# FPGAConfig.net
KiCad netlist of a schematic drawn in Altium Designer
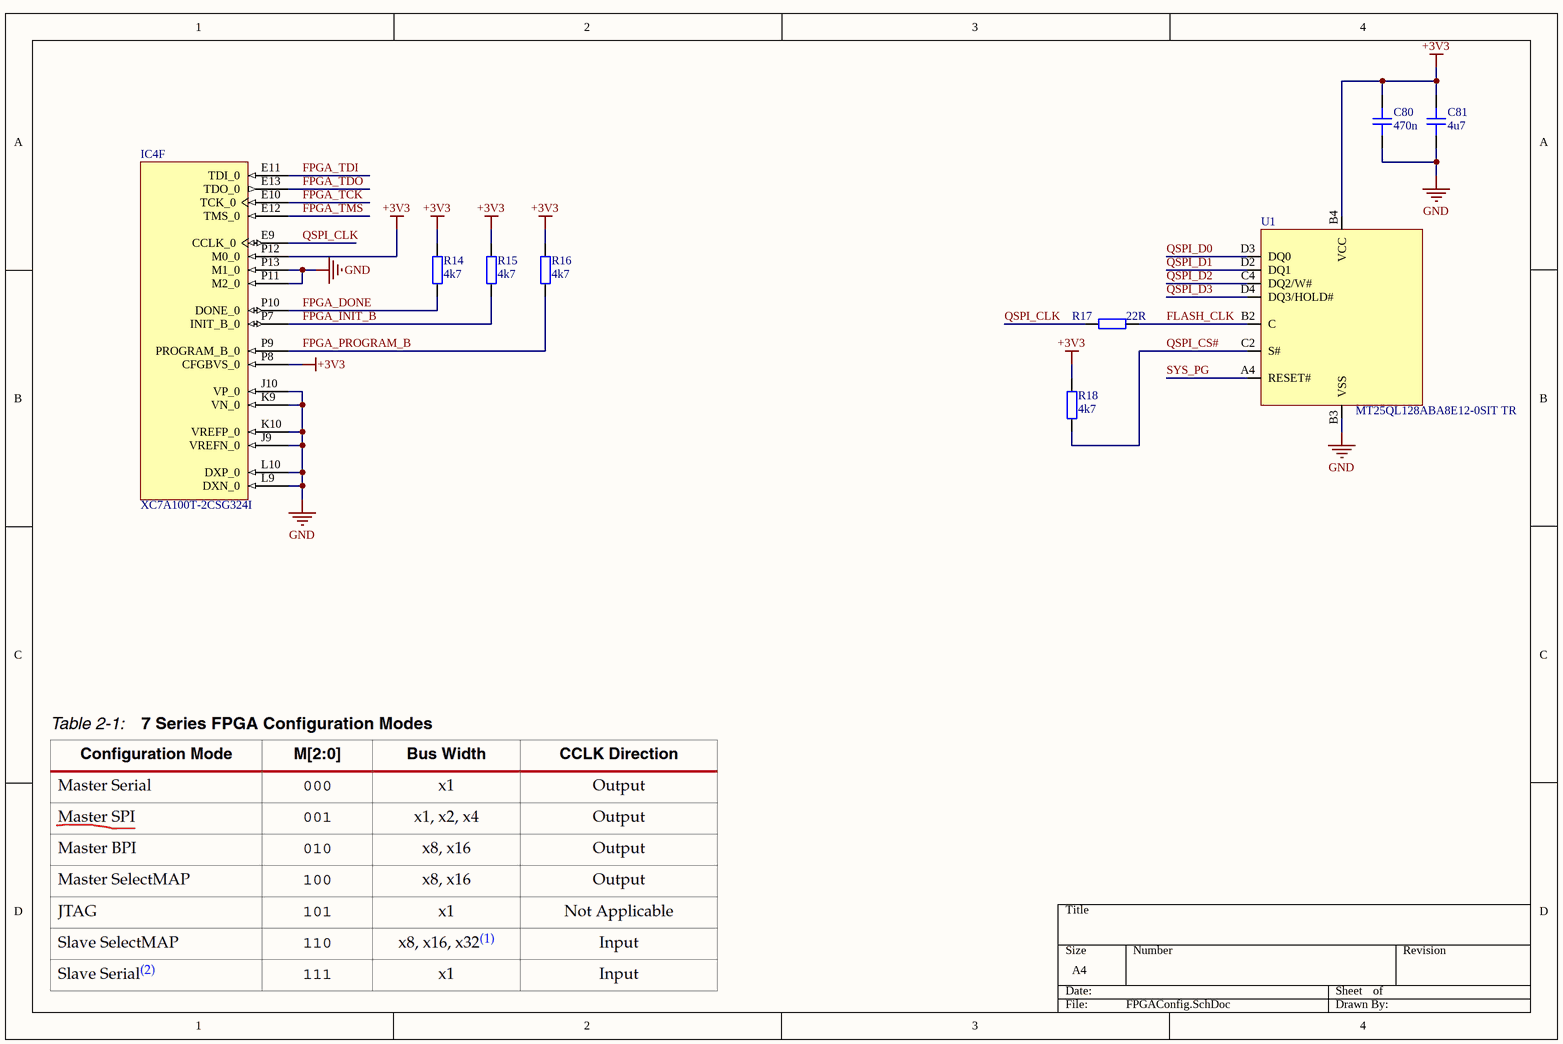
[diagram p0: FPGAConfig.SchDoc]

(export (version "E")
  (design (tool "Eeschema 10.0.6"))
  (components
    (comp (ref "C80")
      (value "470n")
      (footprint "CAP_0201")
      (description "Capacitor SMD 0201")
      (libsource (lib "Schematic-Lib-PhilsLab") (part "CAP_0201"))
    )
    (comp (ref "C81")
      (value "4u7")
      (footprint "CAP_0402")
      (description "Capacitor SMD 0402")
      (libsource (lib "Schematic-Lib-PhilsLab") (part "CAP_0402"))
    )
    (comp (ref "IC4")
      (value "XC7A100T-2CSG324I")
      (footprint "CSG324")
      (description "Artix-7 FPGA, 210 User I/Os, 0 GTP, 324-Ball BGA, Speed Grade 2, Industrial Grade, Pb-Free")
      (fields (field (name "GENERIC PART NUMBER") "XC7A100T") (field (name "MANUFACTURER") "Xilinx"))
      (libsource (lib "Schematic-Lib-PhilsLab") (part "XC7A100T-2CSG324I"))
    )
    (comp (ref "R14")
      (value "4k7")
      (footprint "RES_0201")
      (description "Resistor SMD 0201")
      (libsource (lib "Schematic-Lib-PhilsLab") (part "RES_0201"))
    )
    (comp (ref "R15")
      (value "4k7")
      (footprint "RES_0201")
      (description "Resistor SMD 0201")
      (libsource (lib "Schematic-Lib-PhilsLab") (part "RES_0201"))
    )
    (comp (ref "R16")
      (value "4k7")
      (footprint "RES_0201")
      (description "Resistor SMD 0201")
      (libsource (lib "Schematic-Lib-PhilsLab") (part "RES_0201"))
    )
    (comp (ref "R17")
      (value "22R")
      (footprint "RES_0201")
      (description "Resistor SMD 0201")
      (libsource (lib "Schematic-Lib-PhilsLab") (part "RES_0201"))
    )
    (comp (ref "R18")
      (value "4k7")
      (footprint "RES_0201")
      (description "Resistor SMD 0201")
      (libsource (lib "Schematic-Lib-PhilsLab") (part "RES_0201"))
    )
    (comp (ref "U1")
      (value "MT25QL128ABA8E12-0SIT TR")
      (footprint "T-PBGA-5x5-6x8-24")
      (description "NOR Flash QSPI 128 Mbit T-PBGA-24")
      (fields (field (name "MANUFACTURER") "Micron Technology"))
      (libsource (lib "Schematic-Lib-PhilsLab") (part "MT25QL128ABA8E12-0SIT"))
    )
  )
  (nets
    (net (code "1") (name "+3V3") (class "Default")
      (node (ref "C80") (pin "2") (pinfunction "2_2") (pintype "passive"))
      (node (ref "C81") (pin "2") (pinfunction "2_2") (pintype "passive"))
      (node (ref "IC4") (pin "P12") (pinfunction "M0_0_P12") (pintype "input"))
      (node (ref "IC4") (pin "P8") (pinfunction "CFGBVS_0_P8") (pintype "input"))
      (node (ref "R14") (pin "2") (pinfunction "2_2") (pintype "passive"))
      (node (ref "R15") (pin "2") (pinfunction "2_2") (pintype "passive"))
      (node (ref "R16") (pin "2") (pinfunction "2_2") (pintype "passive"))
      (node (ref "R18") (pin "2") (pinfunction "2_2") (pintype "passive"))
      (node (ref "U1") (pin "B4") (pinfunction "VCC_B4") (pintype "passive"))
    )
    (net (code "2") (name "/FLASH_CLK") (class "Default")
      (node (ref "R17") (pin "1") (pinfunction "1_1") (pintype "passive"))
      (node (ref "U1") (pin "B2") (pinfunction "C_B2") (pintype "passive"))
    )
    (net (code "3") (name "/FPGA_DONE") (class "Default")
      (node (ref "IC4") (pin "P10") (pinfunction "DONE_0_P10") (pintype "bidirectional"))
      (node (ref "R14") (pin "1") (pinfunction "1_1") (pintype "passive"))
    )
    (net (code "4") (name "/FPGA_INIT_B") (class "Default")
      (node (ref "IC4") (pin "P7") (pinfunction "INIT_B_0_P7") (pintype "bidirectional"))
      (node (ref "R15") (pin "1") (pinfunction "1_1") (pintype "passive"))
    )
    (net (code "5") (name "/FPGA_PROGRAM_B") (class "Default")
      (node (ref "IC4") (pin "P9") (pinfunction "PROGRAM_B_0_P9") (pintype "input"))
      (node (ref "R16") (pin "1") (pinfunction "1_1") (pintype "passive"))
    )
    (net (code "6") (name "/FPGA_TCK") (class "Default")
      (node (ref "IC4") (pin "E10") (pinfunction "TCK_0_E10") (pintype "input"))
    )
    (net (code "7") (name "/FPGA_TDI") (class "Default")
      (node (ref "IC4") (pin "E11") (pinfunction "TDI_0_E11") (pintype "input"))
    )
    (net (code "8") (name "/FPGA_TDO") (class "Default")
      (node (ref "IC4") (pin "E13") (pinfunction "TDO_0_E13") (pintype "output"))
    )
    (net (code "9") (name "/FPGA_TMS") (class "Default")
      (node (ref "IC4") (pin "E12") (pinfunction "TMS_0_E12") (pintype "input"))
    )
    (net (code "10") (name "/QSPI_CLK") (class "Default")
      (node (ref "IC4") (pin "E9") (pinfunction "CCLK_0_E9") (pintype "bidirectional"))
      (node (ref "R17") (pin "2") (pinfunction "2_2") (pintype "passive"))
    )
    (net (code "11") (name "/QSPI_CS#") (class "Default")
      (node (ref "R18") (pin "1") (pinfunction "1_1") (pintype "passive"))
      (node (ref "U1") (pin "C2") (pinfunction "S#_C2") (pintype "passive"))
    )
    (net (code "12") (name "/QSPI_D0") (class "Default")
      (node (ref "U1") (pin "D3") (pinfunction "DQ0_D3") (pintype "passive"))
    )
    (net (code "13") (name "/QSPI_D1") (class "Default")
      (node (ref "U1") (pin "D2") (pinfunction "DQ1_D2") (pintype "passive"))
    )
    (net (code "14") (name "/QSPI_D2") (class "Default")
      (node (ref "U1") (pin "C4") (pinfunction "DQ2/W#_C4") (pintype "passive"))
    )
    (net (code "15") (name "/QSPI_D3") (class "Default")
      (node (ref "U1") (pin "D4") (pinfunction "DQ3/HOLD#_D4") (pintype "passive"))
    )
    (net (code "16") (name "/SYS_PG") (class "Default")
      (node (ref "U1") (pin "A4") (pinfunction "RESET#_A4") (pintype "passive"))
    )
    (net (code "17") (name "GND") (class "Default")
      (node (ref "C80") (pin "1") (pinfunction "1_1") (pintype "passive"))
      (node (ref "C81") (pin "1") (pinfunction "1_1") (pintype "passive"))
      (node (ref "IC4") (pin "J10") (pinfunction "VP_0_J10") (pintype "input"))
      (node (ref "IC4") (pin "J9") (pinfunction "VREFN_0_J9") (pintype "input"))
      (node (ref "IC4") (pin "K10") (pinfunction "VREFP_0_K10") (pintype "input"))
      (node (ref "IC4") (pin "K9") (pinfunction "VN_0_K9") (pintype "input"))
      (node (ref "IC4") (pin "L10") (pinfunction "DXP_0_L10") (pintype "input"))
      (node (ref "IC4") (pin "L9") (pinfunction "DXN_0_L9") (pintype "input"))
      (node (ref "IC4") (pin "P11") (pinfunction "M2_0_P11") (pintype "input"))
      (node (ref "IC4") (pin "P13") (pinfunction "M1_0_P13") (pintype "input"))
      (node (ref "U1") (pin "B3") (pinfunction "VSS_B3") (pintype "passive"))
    )
  )
)
